# Echo_locator.net
KiCad netlist of a schematic drawn in EAGLE
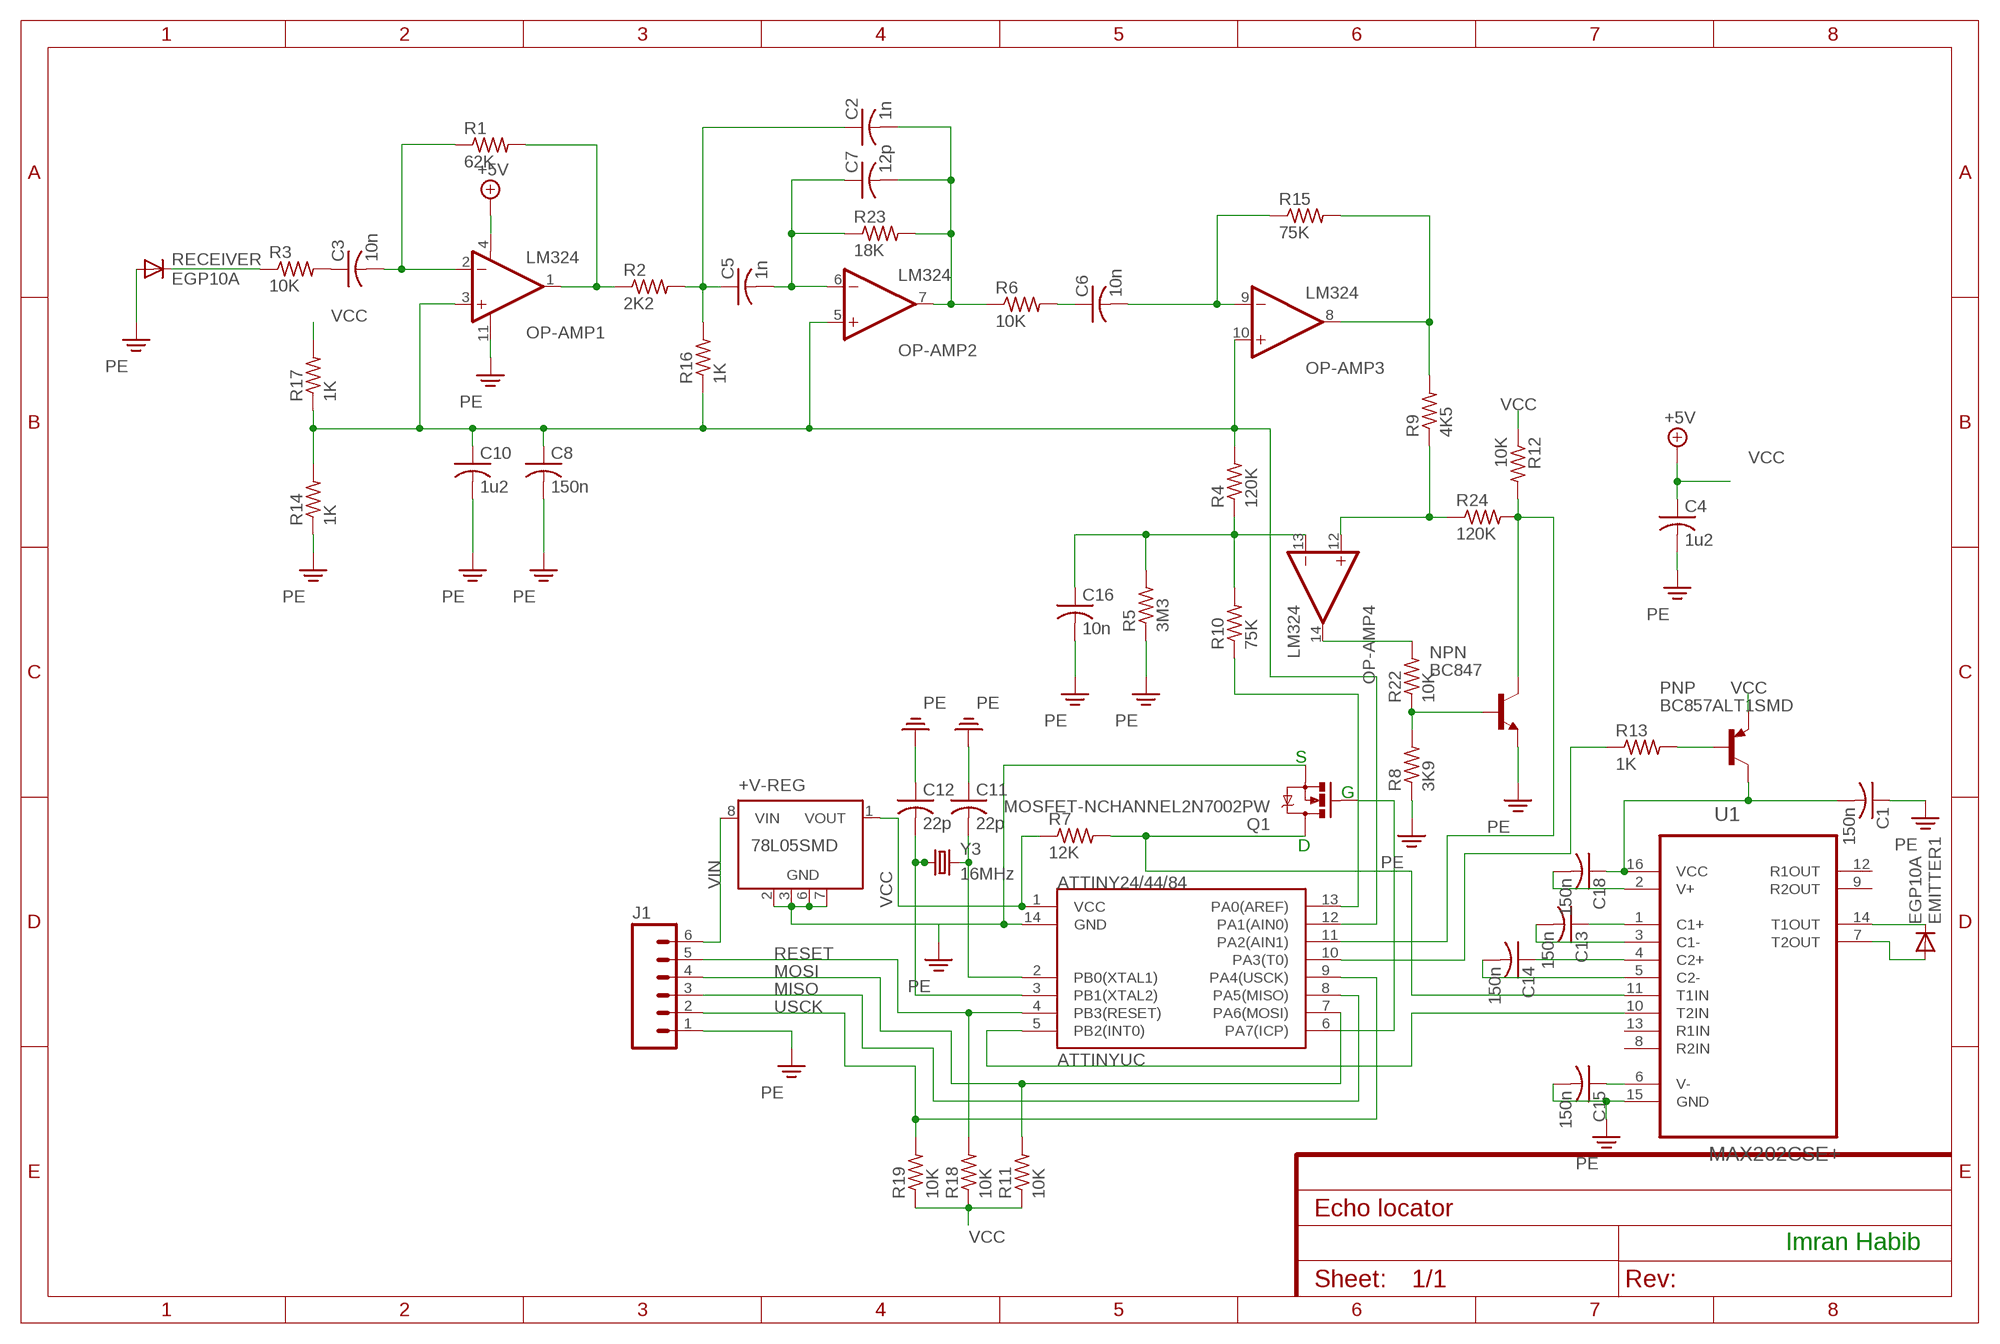
[diagram p0: schematic, sheet 1]

(export (version "E")
  (design (tool "Eeschema 10.0.6"))
  (components
    (comp (ref "+V-REG")
      (value "78L05SMD")
      (footprint "eagle-import:SO08")
      (libsource (lib "eagle-import") (part "78LSMD05"))
    )
    (comp (ref "ATTINYUC")
      (value "ATTINY24")
      (footprint "eagle-import:SOIC-14")
      (libsource (lib "eagle-import") (part "ATTINY24"))
    )
    (comp (ref "C1")
      (value "150n")
      (footprint "eagle-import:C0805")
      (libsource (lib "eagle-import") (part "C-USC0805"))
    )
    (comp (ref "C2")
      (value "1n")
      (footprint "eagle-import:C0805")
      (libsource (lib "eagle-import") (part "C-USC0805"))
    )
    (comp (ref "C3")
      (value "10n")
      (footprint "eagle-import:C0805")
      (libsource (lib "eagle-import") (part "C-USC0805"))
    )
    (comp (ref "C4")
      (value "1u2")
      (footprint "eagle-import:C0805")
      (libsource (lib "eagle-import") (part "C-USC0805"))
    )
    (comp (ref "C5")
      (value "1n")
      (footprint "eagle-import:C0805")
      (libsource (lib "eagle-import") (part "C-USC0805"))
    )
    (comp (ref "C6")
      (value "10n")
      (footprint "eagle-import:C0805")
      (libsource (lib "eagle-import") (part "C-USC0805"))
    )
    (comp (ref "C7")
      (value "12p")
      (footprint "eagle-import:C0805")
      (libsource (lib "eagle-import") (part "C-USC0805"))
    )
    (comp (ref "C8")
      (value "150n")
      (footprint "eagle-import:C0805")
      (libsource (lib "eagle-import") (part "C-USC0805"))
    )
    (comp (ref "C10")
      (value "1u2")
      (footprint "eagle-import:C0805")
      (libsource (lib "eagle-import") (part "C-USC0805"))
    )
    (comp (ref "C11")
      (value "22p")
      (footprint "eagle-import:C0805")
      (libsource (lib "eagle-import") (part "C-USC0805"))
    )
    (comp (ref "C12")
      (value "22p")
      (footprint "eagle-import:C0805")
      (libsource (lib "eagle-import") (part "C-USC0805"))
    )
    (comp (ref "C13")
      (value "150n")
      (footprint "eagle-import:C0805")
      (libsource (lib "eagle-import") (part "C-USC0805"))
    )
    (comp (ref "C14")
      (value "150n")
      (footprint "eagle-import:C0805")
      (libsource (lib "eagle-import") (part "C-USC0805"))
    )
    (comp (ref "C15")
      (value "150n")
      (footprint "eagle-import:C0805")
      (libsource (lib "eagle-import") (part "C-USC0805"))
    )
    (comp (ref "C16")
      (value "10n")
      (footprint "eagle-import:C0805")
      (libsource (lib "eagle-import") (part "C-USC0805"))
    )
    (comp (ref "C18")
      (value "150n")
      (footprint "eagle-import:C0805")
      (libsource (lib "eagle-import") (part "C-USC0805"))
    )
    (comp (ref "EMITTER1")
      (value "EGP10A")
      (footprint "eagle-import:DO41-10")
      (libsource (lib "eagle-import") (part "EGP10A"))
    )
    (comp (ref "J1")
      (value "M06LONGPADS")
      (footprint "eagle-import:1X06_LONGPADS")
      (libsource (lib "eagle-import") (part "M06LONGPADS"))
    )
    (comp (ref "NPN")
      (value "BC847")
      (footprint "eagle-import:SOT23")
      (libsource (lib "eagle-import") (part "BC847"))
    )
    (comp (ref "OP-AMP")
      (value "LM324")
      (footprint "eagle-import:SOIC-14")
      (libsource (lib "eagle-import") (part "LM324"))
    )
    (comp (ref "PNP")
      (value "BC857ALT1SMD")
      (footprint "eagle-import:SOT23-BEC")
      (libsource (lib "eagle-import") (part "BC857SMDALT1"))
    )
    (comp (ref "Q1")
      (value "MOSFET-NCHANNEL2N7002PW")
      (footprint "eagle-import:SOT323")
      (libsource (lib "eagle-import") (part "MOSFET-NCHANNEL2N7002PW"))
    )
    (comp (ref "R1")
      (value "62K")
      (footprint "eagle-import:M2012")
      (libsource (lib "eagle-import") (part "R-US_M2012"))
    )
    (comp (ref "R2")
      (value "2K2")
      (footprint "eagle-import:M2012")
      (libsource (lib "eagle-import") (part "R-US_M2012"))
    )
    (comp (ref "R3")
      (value "10K")
      (footprint "eagle-import:M2012")
      (libsource (lib "eagle-import") (part "R-US_M2012"))
    )
    (comp (ref "R4")
      (value "120K")
      (footprint "eagle-import:M2012")
      (libsource (lib "eagle-import") (part "R-US_M2012"))
    )
    (comp (ref "R5")
      (value "3M3")
      (footprint "eagle-import:M2012")
      (libsource (lib "eagle-import") (part "R-US_M2012"))
    )
    (comp (ref "R6")
      (value "10K")
      (footprint "eagle-import:M2012")
      (libsource (lib "eagle-import") (part "R-US_M2012"))
    )
    (comp (ref "R7")
      (value "12K")
      (footprint "eagle-import:M0805")
      (libsource (lib "eagle-import") (part "R-US_M0805"))
    )
    (comp (ref "R8")
      (value "3K9")
      (footprint "eagle-import:M2012")
      (libsource (lib "eagle-import") (part "R-US_M2012"))
    )
    (comp (ref "R9")
      (value "4K5")
      (footprint "eagle-import:M2012")
      (libsource (lib "eagle-import") (part "R-US_M2012"))
    )
    (comp (ref "R10")
      (value "75K")
      (footprint "eagle-import:M2012")
      (libsource (lib "eagle-import") (part "R-US_M2012"))
    )
    (comp (ref "R11")
      (value "10K")
      (footprint "eagle-import:M2012")
      (libsource (lib "eagle-import") (part "R-US_M2012"))
    )
    (comp (ref "R12")
      (value "10K")
      (footprint "eagle-import:M2012")
      (libsource (lib "eagle-import") (part "R-US_M2012"))
    )
    (comp (ref "R13")
      (value "1K")
      (footprint "eagle-import:M2012")
      (libsource (lib "eagle-import") (part "R-US_M2012"))
    )
    (comp (ref "R14")
      (value "1K")
      (footprint "eagle-import:M2012")
      (libsource (lib "eagle-import") (part "R-US_M2012"))
    )
    (comp (ref "R15")
      (value "75K")
      (footprint "eagle-import:M2012")
      (libsource (lib "eagle-import") (part "R-US_M2012"))
    )
    (comp (ref "R16")
      (value "1K")
      (footprint "eagle-import:M2012")
      (libsource (lib "eagle-import") (part "R-US_M2012"))
    )
    (comp (ref "R17")
      (value "1K")
      (footprint "eagle-import:M2012")
      (libsource (lib "eagle-import") (part "R-US_M2012"))
    )
    (comp (ref "R18")
      (value "10K")
      (footprint "eagle-import:M2012")
      (libsource (lib "eagle-import") (part "R-US_M2012"))
    )
    (comp (ref "R19")
      (value "10K")
      (footprint "eagle-import:M2012")
      (libsource (lib "eagle-import") (part "R-US_M2012"))
    )
    (comp (ref "R22")
      (value "10K")
      (footprint "eagle-import:M2012")
      (libsource (lib "eagle-import") (part "R-US_M2012"))
    )
    (comp (ref "R23")
      (value "18K")
      (footprint "eagle-import:M2012")
      (libsource (lib "eagle-import") (part "R-US_M2012"))
    )
    (comp (ref "R24")
      (value "120K")
      (footprint "eagle-import:M2012")
      (libsource (lib "eagle-import") (part "R-US_M2012"))
    )
    (comp (ref "RECEIVER")
      (value "EGP10A")
      (footprint "eagle-import:DO41-10")
      (libsource (lib "eagle-import") (part "EGP10A"))
    )
    (comp (ref "U1")
      (value "MAX202CSE+")
      (footprint "eagle-import:SOIC127P600X175-16N")
      (libsource (lib "eagle-import") (part "MAX202CSE+"))
    )
    (comp (ref "Y3")
      (value "16MHz")
      (footprint "eagle-import:HC49US")
      (libsource (lib "eagle-import") (part "CRYSTALHC49US"))
    )
  )
  (nets
    (net (code "1") (name "+5V") (class "Default")
      (node (ref "+V-REG") (pin "1") (pinfunction "VOUT_1") (pintype "output"))
      (node (ref "ATTINYUC") (pin "1") (pinfunction "VCC_1") (pintype "bidirectional"))
      (node (ref "C4") (pin "1") (pinfunction "1_1") (pintype "passive"))
      (node (ref "OP-AMP") (pin "4") (pinfunction "V+_4") (pintype "power_in"))
      (node (ref "PNP") (pin "E") (pinfunction "E_E") (pintype "passive"))
      (node (ref "R11") (pin "1") (pinfunction "1_1") (pintype "passive"))
      (node (ref "R12") (pin "1") (pinfunction "1_1") (pintype "passive"))
      (node (ref "R17") (pin "2") (pinfunction "2_2") (pintype "passive"))
      (node (ref "R18") (pin "1") (pinfunction "1_1") (pintype "passive"))
      (node (ref "R19") (pin "1") (pinfunction "1_1") (pintype "passive"))
      (node (ref "R7") (pin "1") (pinfunction "1_1") (pintype "passive"))
    )
    (net (code "2") (name "/MISO") (class "Default")
      (node (ref "ATTINYUC") (pin "8") (pinfunction "PA5(MISO)_8") (pintype "bidirectional"))
      (node (ref "J1") (pin "3") (pinfunction "3_3") (pintype "passive"))
    )
    (net (code "3") (name "/MOSI") (class "Default")
      (node (ref "ATTINYUC") (pin "7") (pinfunction "PA6(MOSI)_7") (pintype "bidirectional"))
      (node (ref "J1") (pin "4") (pinfunction "4_4") (pintype "passive"))
      (node (ref "R11") (pin "2") (pinfunction "2_2") (pintype "passive"))
    )
    (net (code "4") (name "/RESET") (class "Default")
      (node (ref "ATTINYUC") (pin "4") (pinfunction "PB3(RESET)_4") (pintype "bidirectional"))
      (node (ref "J1") (pin "5") (pinfunction "5_5") (pintype "passive"))
      (node (ref "R18") (pin "2") (pinfunction "2_2") (pintype "passive"))
    )
    (net (code "5") (name "/USCK") (class "Default")
      (node (ref "ATTINYUC") (pin "9") (pinfunction "PA4(USCK)_9") (pintype "bidirectional"))
      (node (ref "J1") (pin "2") (pinfunction "2_2") (pintype "passive"))
      (node (ref "R19") (pin "2") (pinfunction "2_2") (pintype "passive"))
    )
    (net (code "6") (name "/VIN") (class "Default")
      (node (ref "+V-REG") (pin "8") (pinfunction "VIN_8") (pintype "passive"))
      (node (ref "J1") (pin "6") (pinfunction "6_6") (pintype "passive"))
    )
    (net (code "7") (name "Net-(ATTINYUC-PA0(AREF))") (class "Default")
      (node (ref "ATTINYUC") (pin "13") (pinfunction "PA0(AREF)_13") (pintype "bidirectional"))
      (node (ref "R10") (pin "1") (pinfunction "1_1") (pintype "passive"))
    )
    (net (code "8") (name "Net-(ATTINYUC-PA1(AIN0))") (class "Default")
      (node (ref "ATTINYUC") (pin "12") (pinfunction "PA1(AIN0)_12") (pintype "bidirectional"))
      (node (ref "C10") (pin "1") (pinfunction "1_1") (pintype "passive"))
      (node (ref "C8") (pin "1") (pinfunction "1_1") (pintype "passive"))
      (node (ref "OP-AMP") (pin "10") (pinfunction "+IN_10") (pintype "input"))
      (node (ref "OP-AMP") (pin "3") (pinfunction "+IN_3") (pintype "input"))
      (node (ref "OP-AMP") (pin "5") (pinfunction "+IN_5") (pintype "input"))
      (node (ref "R14") (pin "2") (pinfunction "2_2") (pintype "passive"))
      (node (ref "R16") (pin "1") (pinfunction "1_1") (pintype "passive"))
      (node (ref "R17") (pin "1") (pinfunction "1_1") (pintype "passive"))
      (node (ref "R4") (pin "2") (pinfunction "2_2") (pintype "passive"))
    )
    (net (code "9") (name "Net-(ATTINYUC-PA2(AIN1))") (class "Default")
      (node (ref "ATTINYUC") (pin "11") (pinfunction "PA2(AIN1)_11") (pintype "bidirectional"))
      (node (ref "NPN") (pin "3") (pinfunction "C_3") (pintype "passive"))
      (node (ref "R12") (pin "2") (pinfunction "2_2") (pintype "passive"))
      (node (ref "R24") (pin "2") (pinfunction "2_2") (pintype "passive"))
    )
    (net (code "10") (name "Net-(ATTINYUC-PA3(T0))") (class "Default")
      (node (ref "ATTINYUC") (pin "10") (pinfunction "PA3(T0)_10") (pintype "bidirectional"))
      (node (ref "R13") (pin "1") (pinfunction "1_1") (pintype "passive"))
    )
    (net (code "11") (name "Net-(ATTINYUC-PA7(ICP))") (class "Default")
      (node (ref "ATTINYUC") (pin "6") (pinfunction "PA7(ICP)_6") (pintype "bidirectional"))
      (node (ref "Q1") (pin "1") (pinfunction "G_1") (pintype "passive"))
    )
    (net (code "12") (name "Net-(ATTINYUC-PB0(XTAL1))") (class "Default")
      (node (ref "ATTINYUC") (pin "2") (pinfunction "PB0(XTAL1)_2") (pintype "bidirectional"))
      (node (ref "C11") (pin "2") (pinfunction "2_2") (pintype "passive"))
      (node (ref "Y3") (pin "2") (pinfunction "2_2") (pintype "passive"))
    )
    (net (code "13") (name "Net-(ATTINYUC-PB1(XTAL2))") (class "Default")
      (node (ref "ATTINYUC") (pin "3") (pinfunction "PB1(XTAL2)_3") (pintype "bidirectional"))
      (node (ref "C12") (pin "2") (pinfunction "2_2") (pintype "passive"))
      (node (ref "Y3") (pin "1") (pinfunction "1_1") (pintype "passive"))
    )
    (net (code "14") (name "Net-(ATTINYUC-PB2(INT0))") (class "Default")
      (node (ref "ATTINYUC") (pin "5") (pinfunction "PB2(INT0)_5") (pintype "bidirectional"))
      (node (ref "U1") (pin "10") (pinfunction "T2IN_10") (pintype "input"))
    )
    (net (code "15") (name "Net-(C2-Pad1)") (class "Default")
      (node (ref "C2") (pin "1") (pinfunction "1_1") (pintype "passive"))
      (node (ref "C5") (pin "1") (pinfunction "1_1") (pintype "passive"))
      (node (ref "R16") (pin "2") (pinfunction "2_2") (pintype "passive"))
      (node (ref "R2") (pin "2") (pinfunction "2_2") (pintype "passive"))
    )
    (net (code "16") (name "Net-(C3-Pad1)") (class "Default")
      (node (ref "C3") (pin "1") (pinfunction "1_1") (pintype "passive"))
      (node (ref "R3") (pin "2") (pinfunction "2_2") (pintype "passive"))
    )
    (net (code "17") (name "Net-(C6-Pad1)") (class "Default")
      (node (ref "C6") (pin "1") (pinfunction "1_1") (pintype "passive"))
      (node (ref "R6") (pin "2") (pinfunction "2_2") (pintype "passive"))
    )
    (net (code "18") (name "Net-(NPN-B)") (class "Default")
      (node (ref "NPN") (pin "1") (pinfunction "B_1") (pintype "passive"))
      (node (ref "R22") (pin "1") (pinfunction "1_1") (pintype "passive"))
      (node (ref "R8") (pin "2") (pinfunction "2_2") (pintype "passive"))
    )
    (net (code "19") (name "Net-(OP-AMPA--IN)") (class "Default")
      (node (ref "C3") (pin "2") (pinfunction "2_2") (pintype "passive"))
      (node (ref "OP-AMP") (pin "2") (pinfunction "-IN_2") (pintype "input"))
      (node (ref "R1") (pin "1") (pinfunction "1_1") (pintype "passive"))
    )
    (net (code "20") (name "Net-(OP-AMPA-OUT)") (class "Default")
      (node (ref "OP-AMP") (pin "1") (pinfunction "OUT_1") (pintype "output"))
      (node (ref "R1") (pin "2") (pinfunction "2_2") (pintype "passive"))
      (node (ref "R2") (pin "1") (pinfunction "1_1") (pintype "passive"))
    )
    (net (code "21") (name "Net-(OP-AMPB--IN)") (class "Default")
      (node (ref "C5") (pin "2") (pinfunction "2_2") (pintype "passive"))
      (node (ref "C7") (pin "1") (pinfunction "1_1") (pintype "passive"))
      (node (ref "OP-AMP") (pin "6") (pinfunction "-IN_6") (pintype "input"))
      (node (ref "R23") (pin "1") (pinfunction "1_1") (pintype "passive"))
    )
    (net (code "22") (name "Net-(OP-AMPB-OUT)") (class "Default")
      (node (ref "C2") (pin "2") (pinfunction "2_2") (pintype "passive"))
      (node (ref "C7") (pin "2") (pinfunction "2_2") (pintype "passive"))
      (node (ref "OP-AMP") (pin "7") (pinfunction "OUT_7") (pintype "output"))
      (node (ref "R23") (pin "2") (pinfunction "2_2") (pintype "passive"))
      (node (ref "R6") (pin "1") (pinfunction "1_1") (pintype "passive"))
    )
    (net (code "23") (name "Net-(OP-AMPC--IN)") (class "Default")
      (node (ref "C6") (pin "2") (pinfunction "2_2") (pintype "passive"))
      (node (ref "OP-AMP") (pin "9") (pinfunction "-IN_9") (pintype "input"))
      (node (ref "R15") (pin "1") (pinfunction "1_1") (pintype "passive"))
    )
    (net (code "24") (name "Net-(OP-AMPC-OUT)") (class "Default")
      (node (ref "OP-AMP") (pin "8") (pinfunction "OUT_8") (pintype "output"))
      (node (ref "R15") (pin "2") (pinfunction "2_2") (pintype "passive"))
      (node (ref "R9") (pin "2") (pinfunction "2_2") (pintype "passive"))
    )
    (net (code "25") (name "Net-(OP-AMPD-+IN)") (class "Default")
      (node (ref "OP-AMP") (pin "12") (pinfunction "+IN_12") (pintype "input"))
      (node (ref "R24") (pin "1") (pinfunction "1_1") (pintype "passive"))
      (node (ref "R9") (pin "1") (pinfunction "1_1") (pintype "passive"))
    )
    (net (code "26") (name "Net-(OP-AMPD--IN)") (class "Default")
      (node (ref "C16") (pin "1") (pinfunction "1_1") (pintype "passive"))
      (node (ref "OP-AMP") (pin "13") (pinfunction "-IN_13") (pintype "input"))
      (node (ref "R10") (pin "2") (pinfunction "2_2") (pintype "passive"))
      (node (ref "R4") (pin "1") (pinfunction "1_1") (pintype "passive"))
      (node (ref "R5") (pin "2") (pinfunction "2_2") (pintype "passive"))
    )
    (net (code "27") (name "Net-(OP-AMPD-OUT)") (class "Default")
      (node (ref "OP-AMP") (pin "14") (pinfunction "OUT_14") (pintype "output"))
      (node (ref "R22") (pin "2") (pinfunction "2_2") (pintype "passive"))
    )
    (net (code "28") (name "Net-(PNP-PadB)") (class "Default")
      (node (ref "PNP") (pin "B") (pinfunction "B_B") (pintype "passive"))
      (node (ref "R13") (pin "2") (pinfunction "2_2") (pintype "passive"))
    )
    (net (code "29") (name "Net-(Q1-D)") (class "Default")
      (node (ref "Q1") (pin "3") (pinfunction "D_3") (pintype "passive"))
      (node (ref "R7") (pin "2") (pinfunction "2_2") (pintype "passive"))
      (node (ref "U1") (pin "11") (pinfunction "T1IN_11") (pintype "input"))
    )
    (net (code "30") (name "Net-(R3-Pad1)") (class "Default")
      (node (ref "R3") (pin "1") (pinfunction "1_1") (pintype "passive"))
      (node (ref "RECEIVER") (pin "C") (pinfunction "C_C") (pintype "passive"))
    )
    (net (code "31") (name "Net-(U1-C1+)") (class "Default")
      (node (ref "C13") (pin "1") (pinfunction "1_1") (pintype "passive"))
      (node (ref "U1") (pin "1") (pinfunction "C1+_1") (pintype "passive"))
    )
    (net (code "32") (name "Net-(U1-C1-)") (class "Default")
      (node (ref "C13") (pin "2") (pinfunction "2_2") (pintype "passive"))
      (node (ref "U1") (pin "3") (pinfunction "C1-_3") (pintype "passive"))
    )
    (net (code "33") (name "Net-(U1-C2+)") (class "Default")
      (node (ref "C14") (pin "1") (pinfunction "1_1") (pintype "passive"))
      (node (ref "U1") (pin "4") (pinfunction "C2+_4") (pintype "passive"))
    )
    (net (code "34") (name "Net-(U1-C2-)") (class "Default")
      (node (ref "C14") (pin "2") (pinfunction "2_2") (pintype "passive"))
      (node (ref "U1") (pin "5") (pinfunction "C2-_5") (pintype "passive"))
    )
    (net (code "35") (name "Net-(U1-T1OUT)") (class "Default")
      (node (ref "EMITTER1") (pin "C") (pinfunction "C_C") (pintype "passive"))
      (node (ref "U1") (pin "14") (pinfunction "T1OUT_14") (pintype "output"))
    )
    (net (code "36") (name "Net-(U1-T2OUT)") (class "Default")
      (node (ref "EMITTER1") (pin "A") (pinfunction "A_A") (pintype "passive"))
      (node (ref "U1") (pin "7") (pinfunction "T2OUT_7") (pintype "output"))
    )
    (net (code "37") (name "Net-(U1-V+)") (class "Default")
      (node (ref "C18") (pin "2") (pinfunction "2_2") (pintype "passive"))
      (node (ref "U1") (pin "2") (pinfunction "V+_2") (pintype "power_in"))
    )
    (net (code "38") (name "Net-(U1-V-)") (class "Default")
      (node (ref "C15") (pin "1") (pinfunction "1_1") (pintype "passive"))
      (node (ref "U1") (pin "6") (pinfunction "V-_6") (pintype "power_in"))
    )
    (net (code "39") (name "Net-(U1-VCC)") (class "Default")
      (node (ref "C1") (pin "2") (pinfunction "2_2") (pintype "passive"))
      (node (ref "C18") (pin "1") (pinfunction "1_1") (pintype "passive"))
      (node (ref "PNP") (pin "C") (pinfunction "C_C") (pintype "passive"))
      (node (ref "U1") (pin "16") (pinfunction "VCC_16") (pintype "power_in"))
    )
    (net (code "40") (name "PE") (class "Default")
      (node (ref "+V-REG") (pin "2") (pinfunction "GND_2") (pintype "power_in"))
      (node (ref "+V-REG") (pin "3") (pinfunction "GND_3") (pintype "power_in"))
      (node (ref "+V-REG") (pin "6") (pinfunction "GND_6") (pintype "power_in"))
      (node (ref "+V-REG") (pin "7") (pinfunction "GND_7") (pintype "power_in"))
      (node (ref "ATTINYUC") (pin "14") (pinfunction "GND_14") (pintype "bidirectional"))
      (node (ref "C1") (pin "1") (pinfunction "1_1") (pintype "passive"))
      (node (ref "C10") (pin "2") (pinfunction "2_2") (pintype "passive"))
      (node (ref "C11") (pin "1") (pinfunction "1_1") (pintype "passive"))
      (node (ref "C12") (pin "1") (pinfunction "1_1") (pintype "passive"))
      (node (ref "C15") (pin "2") (pinfunction "2_2") (pintype "passive"))
      (node (ref "C16") (pin "2") (pinfunction "2_2") (pintype "passive"))
      (node (ref "C4") (pin "2") (pinfunction "2_2") (pintype "passive"))
      (node (ref "C8") (pin "2") (pinfunction "2_2") (pintype "passive"))
      (node (ref "J1") (pin "1") (pinfunction "1_1") (pintype "passive"))
      (node (ref "NPN") (pin "2") (pinfunction "E_2") (pintype "passive"))
      (node (ref "OP-AMP") (pin "11") (pinfunction "V-_11") (pintype "power_in"))
      (node (ref "Q1") (pin "2") (pinfunction "S_2") (pintype "passive"))
      (node (ref "R14") (pin "1") (pinfunction "1_1") (pintype "passive"))
      (node (ref "R5") (pin "1") (pinfunction "1_1") (pintype "passive"))
      (node (ref "R8") (pin "1") (pinfunction "1_1") (pintype "passive"))
      (node (ref "RECEIVER") (pin "A") (pinfunction "A_A") (pintype "passive"))
      (node (ref "U1") (pin "15") (pinfunction "GND_15") (pintype "passive"))
    )
    (net (code "41") (name "unconnected-(U1-R1IN-Pad13)") (class "Default")
      (node (ref "U1") (pin "13") (pinfunction "R1IN_13") (pintype "input"))
    )
    (net (code "42") (name "unconnected-(U1-R1OUT-Pad12)") (class "Default")
      (node (ref "U1") (pin "12") (pinfunction "R1OUT_12") (pintype "output"))
    )
    (net (code "43") (name "unconnected-(U1-R2IN-Pad8)") (class "Default")
      (node (ref "U1") (pin "8") (pinfunction "R2IN_8") (pintype "input"))
    )
    (net (code "44") (name "unconnected-(U1-R2OUT-Pad9)") (class "Default")
      (node (ref "U1") (pin "9") (pinfunction "R2OUT_9") (pintype "output"))
    )
  )
)
